# PROC010B_LC_Filtering_Reference.net
KiCad netlist of a schematic drawn in Altium Designer
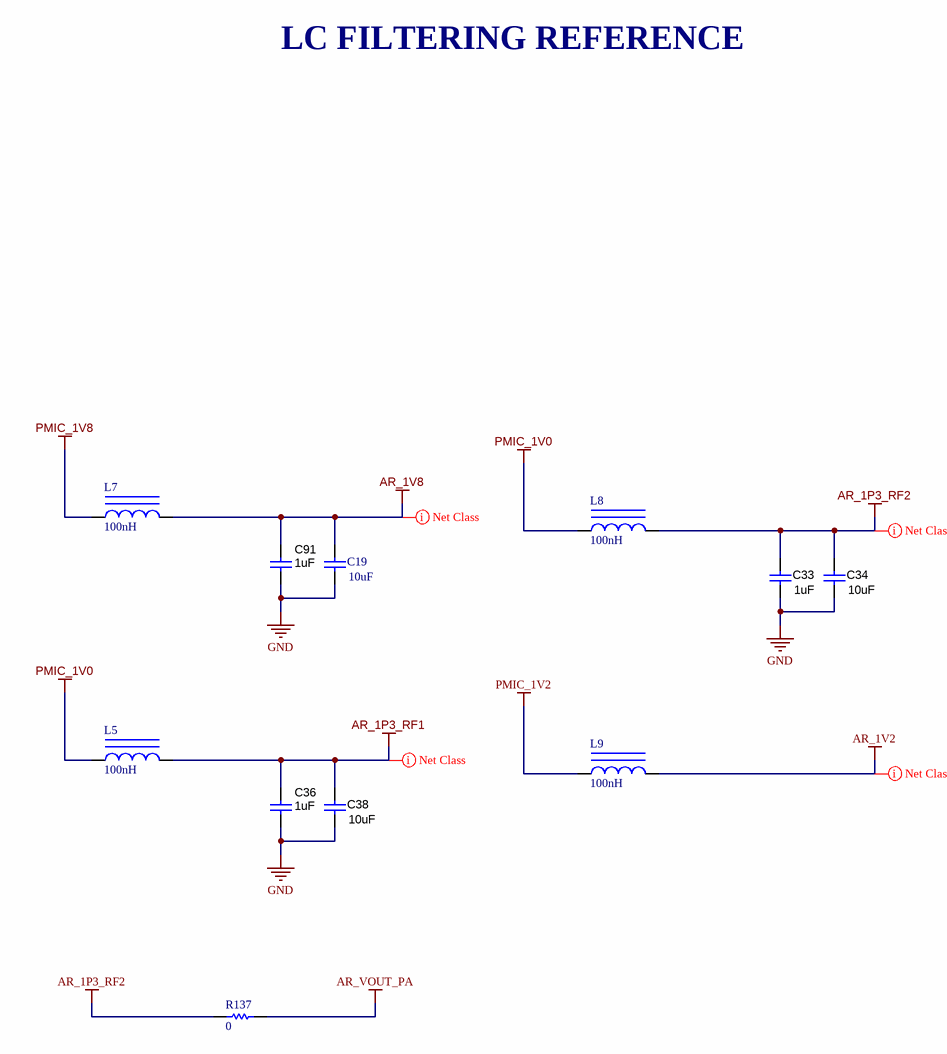
[diagram p0: PROC010B_LC_Filtering_Reference.SchDoc]

(export (version "E")
  (design (tool "Eeschema 10.0.6"))
  (components
    (comp (ref "C19")
      (value "GCM21BR71A106KE22L")
      (footprint "0805_HV")
      (description "CAP, CERM, 10 uF, 10 V, +/- 10%, X7R, 0805")
      (fields
        (field (name "MANUFACTURER") "MuRata")
        (field (name "VALUEDISPLAYED") "10uF")
        (field (name "PUBLISHER") "Texas Instruments")
      )
      (libsource (lib "Altium Vault - TI") (part "Capacitor"))
    )
    (comp (ref "C33")
      (value "GCM188R71C105KA64D")
      (footprint "0603")
      (description "CAP, CERM, 1 uF, 16 V, +/- 10%, X7R, AEC-Q200 Grade 1, 0603")
      (fields
        (field (name "MANUFACTURER") "MuRata")
        (field (name "VALUEDISPLAYED") "1uF")
        (field (name "PUBLISHER") "Texas Instruments")
      )
      (libsource (lib "Altium Vault - TI") (part "Capacitor"))
    )
    (comp (ref "C34")
      (value "GCM21BR71A106KE22L")
      (footprint "0805_HV")
      (description "CAP, CERM, 10 uF, 10 V, +/- 10%, X7R, 0805")
      (fields
        (field (name "MANUFACTURER") "MuRata")
        (field (name "VALUEDISPLAYED") "10uF")
        (field (name "PUBLISHER") "Texas Instruments")
      )
      (libsource (lib "Altium Vault - TI") (part "CMP-0008017-2"))
    )
    (comp (ref "C36")
      (value "GCM188R71C105KA64D")
      (footprint "0603")
      (description "CAP, CERM, 1 uF, 16 V, +/- 10%, X7R, AEC-Q200 Grade 1, 0603")
      (fields
        (field (name "MANUFACTURER") "MuRata")
        (field (name "VALUEDISPLAYED") "1uF")
        (field (name "PUBLISHER") "Texas Instruments")
      )
      (libsource (lib "Altium Vault - TI") (part "Capacitor"))
    )
    (comp (ref "C38")
      (value "GCM21BR71A106KE22L")
      (footprint "0805_HV")
      (description "CAP, CERM, 10 uF, 10 V, +/- 10%, X7R, 0805")
      (fields
        (field (name "MANUFACTURER") "MuRata")
        (field (name "VALUEDISPLAYED") "10uF")
        (field (name "PUBLISHER") "Texas Instruments")
      )
      (libsource (lib "Altium Vault - TI") (part "CMP-0008017-2"))
    )
    (comp (ref "C91")
      (value "GCM188R71C105KA64D")
      (footprint "0603")
      (description "CAP, CERM, 1 uF, 16 V, +/- 10%, X7R, AEC-Q200 Grade 1, 0603")
      (fields
        (field (name "MANUFACTURER") "MuRata")
        (field (name "VALUEDISPLAYED") "1uF")
        (field (name "PUBLISHER") "Texas Instruments")
      )
      (libsource (lib "Altium Vault - TI") (part "Capacitor"))
    )
    (comp (ref "L5")
      (value "NLCV32T-R10M-EFRD")
      (footprint "NLCV32")
      (description "Inductor, Wirewound, Ferrite, 100 nH, 2.85 A, 0.024 ohm, AEC-Q200 Grade 1, SMD")
      (fields (field (name "MANUFACTURER") "TDK") (field (name "VALUEDISPLAYED") "100nH"))
      (libsource (lib "Altium Vault - TI") (part "Inductor_Iron"))
    )
    (comp (ref "L7")
      (value "NLCV32T-R10M-EFRD")
      (footprint "NLCV32")
      (description "Inductor, Wirewound, Ferrite, 100 nH, 2.85 A, 0.024 ohm, AEC-Q200 Grade 1, SMD")
      (fields (field (name "MANUFACTURER") "TDK") (field (name "VALUEDISPLAYED") "100nH"))
      (libsource (lib "Altium Vault - TI") (part "Inductor_Iron"))
    )
    (comp (ref "L8")
      (value "NLCV32T-R10M-EFRD")
      (footprint "NLCV32")
      (description "Inductor, Wirewound, Ferrite, 100 nH, 2.85 A, 0.024 ohm, AEC-Q200 Grade 1, SMD")
      (fields (field (name "MANUFACTURER") "TDK") (field (name "VALUEDISPLAYED") "100nH"))
      (libsource (lib "Altium Vault - TI") (part "Inductor_Iron"))
    )
    (comp (ref "L9")
      (value "NLCV32T-R10M-EFRD")
      (footprint "NLCV32")
      (description "Inductor, Wirewound, Ferrite, 100 nH, 2.85 A, 0.024 ohm, AEC-Q200 Grade 1, SMD")
      (fields (field (name "MANUFACTURER") "TDK") (field (name "VALUEDISPLAYED") "100nH"))
      (libsource (lib "Altium Vault - TI") (part "Inductor_Iron"))
    )
    (comp (ref "R137")
      (value "MCT06030Z0000ZP500")
      (footprint "0603")
      (description "RES, 0, 5%, 0.125 W, 0603")
      (fields
        (field (name "MANUFACTURER") "Vishay/Beyschlag")
        (field (name "VALUEDISPLAYED") "0")
        (field (name "PUBLISHER") "Texas Instruments")
      )
      (libsource (lib "Altium Vault - TI") (part "CMP-0025884-3"))
    )
  )
  (nets
    (net (code "1") (name "AR_1P3_RF1") (class "Default")
      (node (ref "C36") (pin "2") (pinfunction "2_2") (pintype "passive"))
      (node (ref "C38") (pin "2") (pinfunction "2_2") (pintype "passive"))
      (node (ref "L5") (pin "2") (pinfunction "2_2") (pintype "passive"))
    )
    (net (code "2") (name "AR_1P3_RF2") (class "Default")
      (node (ref "C33") (pin "2") (pinfunction "2_2") (pintype "passive"))
      (node (ref "C34") (pin "2") (pinfunction "2_2") (pintype "passive"))
      (node (ref "L8") (pin "2") (pinfunction "2_2") (pintype "passive"))
      (node (ref "R137") (pin "1") (pinfunction "1_1") (pintype "passive"))
    )
    (net (code "3") (name "AR_1V2") (class "Default")
      (node (ref "L9") (pin "2") (pinfunction "2_2") (pintype "passive"))
    )
    (net (code "4") (name "AR_1V8") (class "Default")
      (node (ref "C19") (pin "1") (pinfunction "1_1") (pintype "passive"))
      (node (ref "C91") (pin "2") (pinfunction "2_2") (pintype "passive"))
      (node (ref "L7") (pin "2") (pinfunction "2_2") (pintype "passive"))
    )
    (net (code "5") (name "AR_VOUT_PA") (class "Default")
      (node (ref "R137") (pin "2") (pinfunction "2_2") (pintype "passive"))
    )
    (net (code "6") (name "GND") (class "Default")
      (node (ref "C19") (pin "2") (pinfunction "2_2") (pintype "passive"))
      (node (ref "C33") (pin "1") (pinfunction "1_1") (pintype "passive"))
      (node (ref "C34") (pin "1") (pinfunction "1_1") (pintype "passive"))
      (node (ref "C36") (pin "1") (pinfunction "1_1") (pintype "passive"))
      (node (ref "C38") (pin "1") (pinfunction "1_1") (pintype "passive"))
      (node (ref "C91") (pin "1") (pinfunction "1_1") (pintype "passive"))
    )
    (net (code "7") (name "PMIC_1V0") (class "Default")
      (node (ref "L5") (pin "1") (pinfunction "1_1") (pintype "passive"))
      (node (ref "L8") (pin "1") (pinfunction "1_1") (pintype "passive"))
    )
    (net (code "8") (name "PMIC_1V2") (class "Default")
      (node (ref "L9") (pin "1") (pinfunction "1_1") (pintype "passive"))
    )
    (net (code "9") (name "PMIC_1V8") (class "Default")
      (node (ref "L7") (pin "1") (pinfunction "1_1") (pintype "passive"))
    )
  )
)
